# CH572Q-DG-R0.net
KiCad netlist of a schematic drawn in Altium Designer
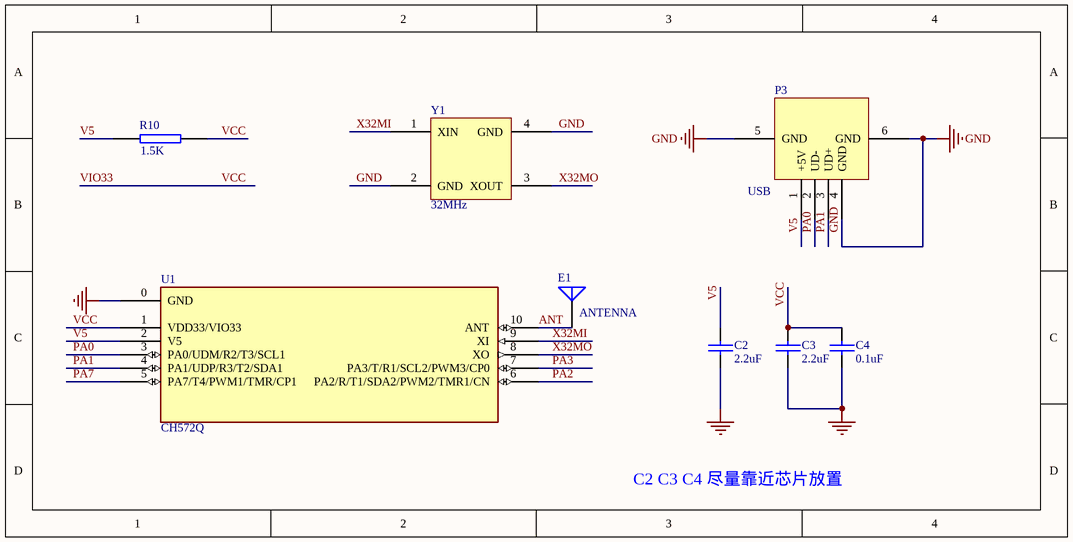
[diagram p0: CH572Q-DG-R0.SchDoc]

(export (version "E")
  (design (tool "Eeschema 10.0.6"))
  (components
    (comp (ref "C2")
      (value "2.2uF")
      (footprint "0402_C")
      (description "Capacitor")
      (libsource (lib "*") (part "CAP"))
    )
    (comp (ref "C3")
      (value "2.2uF")
      (footprint "0402_C")
      (description "Capacitor")
      (libsource (lib "*") (part "CAP"))
    )
    (comp (ref "C4")
      (value "0.1uF")
      (footprint "0402_C")
      (description "Capacitor")
      (libsource (lib "*") (part "CAP"))
    )
    (comp (ref "E1")
      (value "ANTENNA")
      (footprint "ANT-F-1-2.4G-0.8mmFR4")
      (description "Generic Antenna")
      (libsource (lib "*") (part "ANTENNA"))
    )
    (comp (ref "P3") (value "USB") (footprint "USBAM-4P") (libsource (lib "Schlib1") (part "USB")))
    (comp (ref "R10") (value "1.5K") (footprint "0402") (libsource (lib "*") (part "RES2")))
    (comp (ref "U1")
      (value "CH572Q")
      (footprint "DFN10_3X3")
      (description "RISC-V MCU with BLE/2.4GHz Wireless/USB/UART/I2C/PWM/CMP")
      (libsource (lib "DHXXXSCHd") (part "CH572Q"))
    )
    (comp (ref "Y1") (value "32MHz") (footprint "XT2016") (libsource (lib "wch_sch_others") (part "晶体")))
  )
  (nets
    (net (code "1") (name "/ANT") (class "Default")
      (node (ref "E1") (pin "1") (pinfunction "A_1") (pintype "passive"))
      (node (ref "U1") (pin "10") (pinfunction "ANT_10") (pintype "bidirectional"))
    )
    (net (code "2") (name "/PA0") (class "Default")
      (node (ref "P3") (pin "2") (pinfunction "UD-_2") (pintype "passive"))
      (node (ref "U1") (pin "3") (pinfunction "PA0/UDM/R2/T3/SCL1_3") (pintype "bidirectional"))
    )
    (net (code "3") (name "/PA1") (class "Default")
      (node (ref "P3") (pin "3") (pinfunction "UD+_3") (pintype "passive"))
      (node (ref "U1") (pin "4") (pinfunction "PA1/UDP/R3/T2/SDA1_4") (pintype "bidirectional"))
    )
    (net (code "4") (name "/PA2") (class "Default")
      (node (ref "U1") (pin "6") (pinfunction "PA2/R/T1/SDA2/PWM2/TMR1/CN_6") (pintype "bidirectional"))
    )
    (net (code "5") (name "/PA3") (class "Default")
      (node (ref "U1") (pin "7") (pinfunction "PA3/T/R1/SCL2/PWM3/CP0_7") (pintype "bidirectional"))
    )
    (net (code "6") (name "/PA7") (class "Default")
      (node (ref "U1") (pin "5") (pinfunction "PA7/T4/PWM1/TMR/CP1_5") (pintype "bidirectional"))
    )
    (net (code "7") (name "/V5") (class "Default")
      (node (ref "C2") (pin "1") (pinfunction "1_1") (pintype "passive"))
      (node (ref "P3") (pin "1") (pinfunction "+5V_1") (pintype "passive"))
      (node (ref "R10") (pin "1") (pinfunction "1_1") (pintype "passive"))
      (node (ref "U1") (pin "2") (pinfunction "V5_2") (pintype "power_in"))
    )
    (net (code "8") (name "/VCC") (class "Default")
      (node (ref "C3") (pin "1") (pinfunction "1_1") (pintype "passive"))
      (node (ref "C4") (pin "1") (pinfunction "1_1") (pintype "passive"))
      (node (ref "R10") (pin "2") (pinfunction "2_2") (pintype "passive"))
      (node (ref "U1") (pin "1") (pinfunction "VDD33/VIO33_1") (pintype "power_in"))
    )
    (net (code "9") (name "/X32MI") (class "Default")
      (node (ref "U1") (pin "9") (pinfunction "XI_9") (pintype "input"))
      (node (ref "Y1") (pin "1") (pinfunction "XIN_1") (pintype "passive"))
    )
    (net (code "10") (name "/X32MO") (class "Default")
      (node (ref "U1") (pin "8") (pinfunction "XO_8") (pintype "output"))
      (node (ref "Y1") (pin "3") (pinfunction "XOUT_3") (pintype "passive"))
    )
    (net (code "11") (name "GND") (class "Default")
      (node (ref "C2") (pin "2") (pinfunction "2_2") (pintype "passive"))
      (node (ref "C3") (pin "2") (pinfunction "2_2") (pintype "passive"))
      (node (ref "C4") (pin "2") (pinfunction "2_2") (pintype "passive"))
      (node (ref "P3") (pin "4") (pinfunction "GND_4") (pintype "passive"))
      (node (ref "P3") (pin "5") (pinfunction "GND_5") (pintype "passive"))
      (node (ref "P3") (pin "6") (pinfunction "GND_6") (pintype "passive"))
      (node (ref "U1") (pin "0") (pinfunction "GND_0") (pintype "power_in"))
      (node (ref "Y1") (pin "2") (pinfunction "GND_2") (pintype "passive"))
      (node (ref "Y1") (pin "4") (pinfunction "GND_4") (pintype "passive"))
    )
  )
)
